# mistygro_easyeda_2023-10-08.net
KiCad netlist of a schematic drawn in EasyEDA
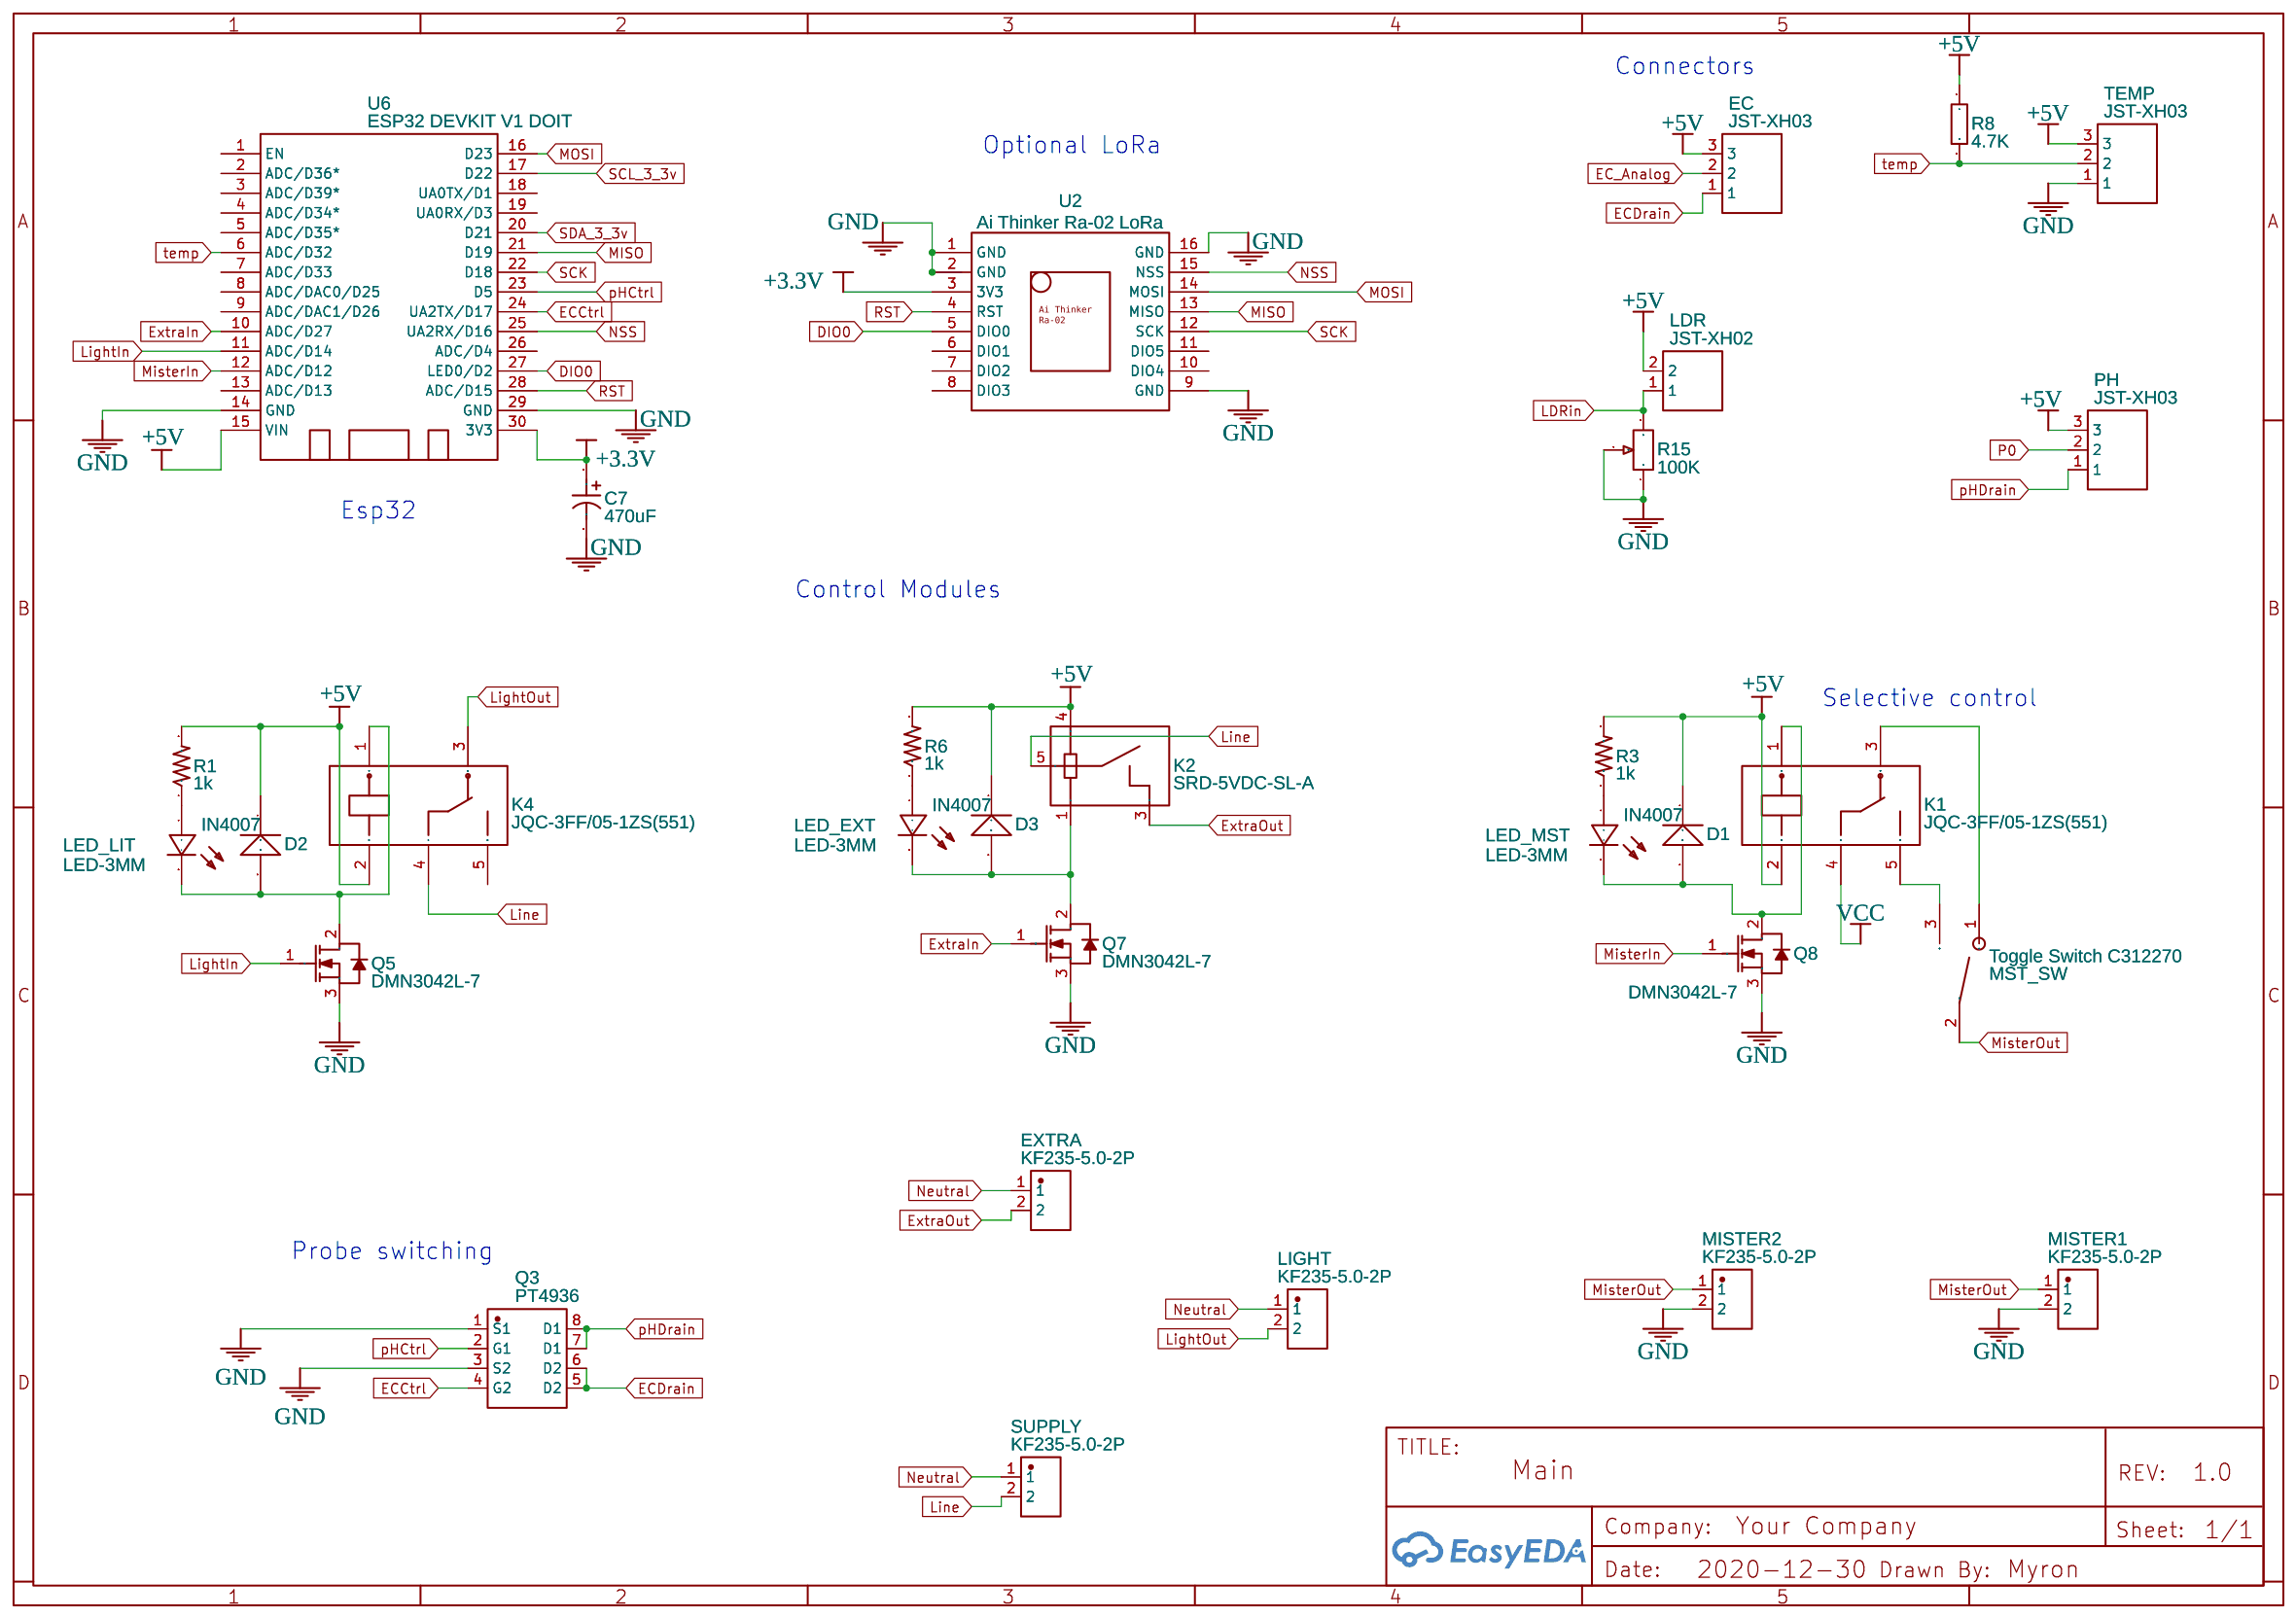
[diagram p0: Main]
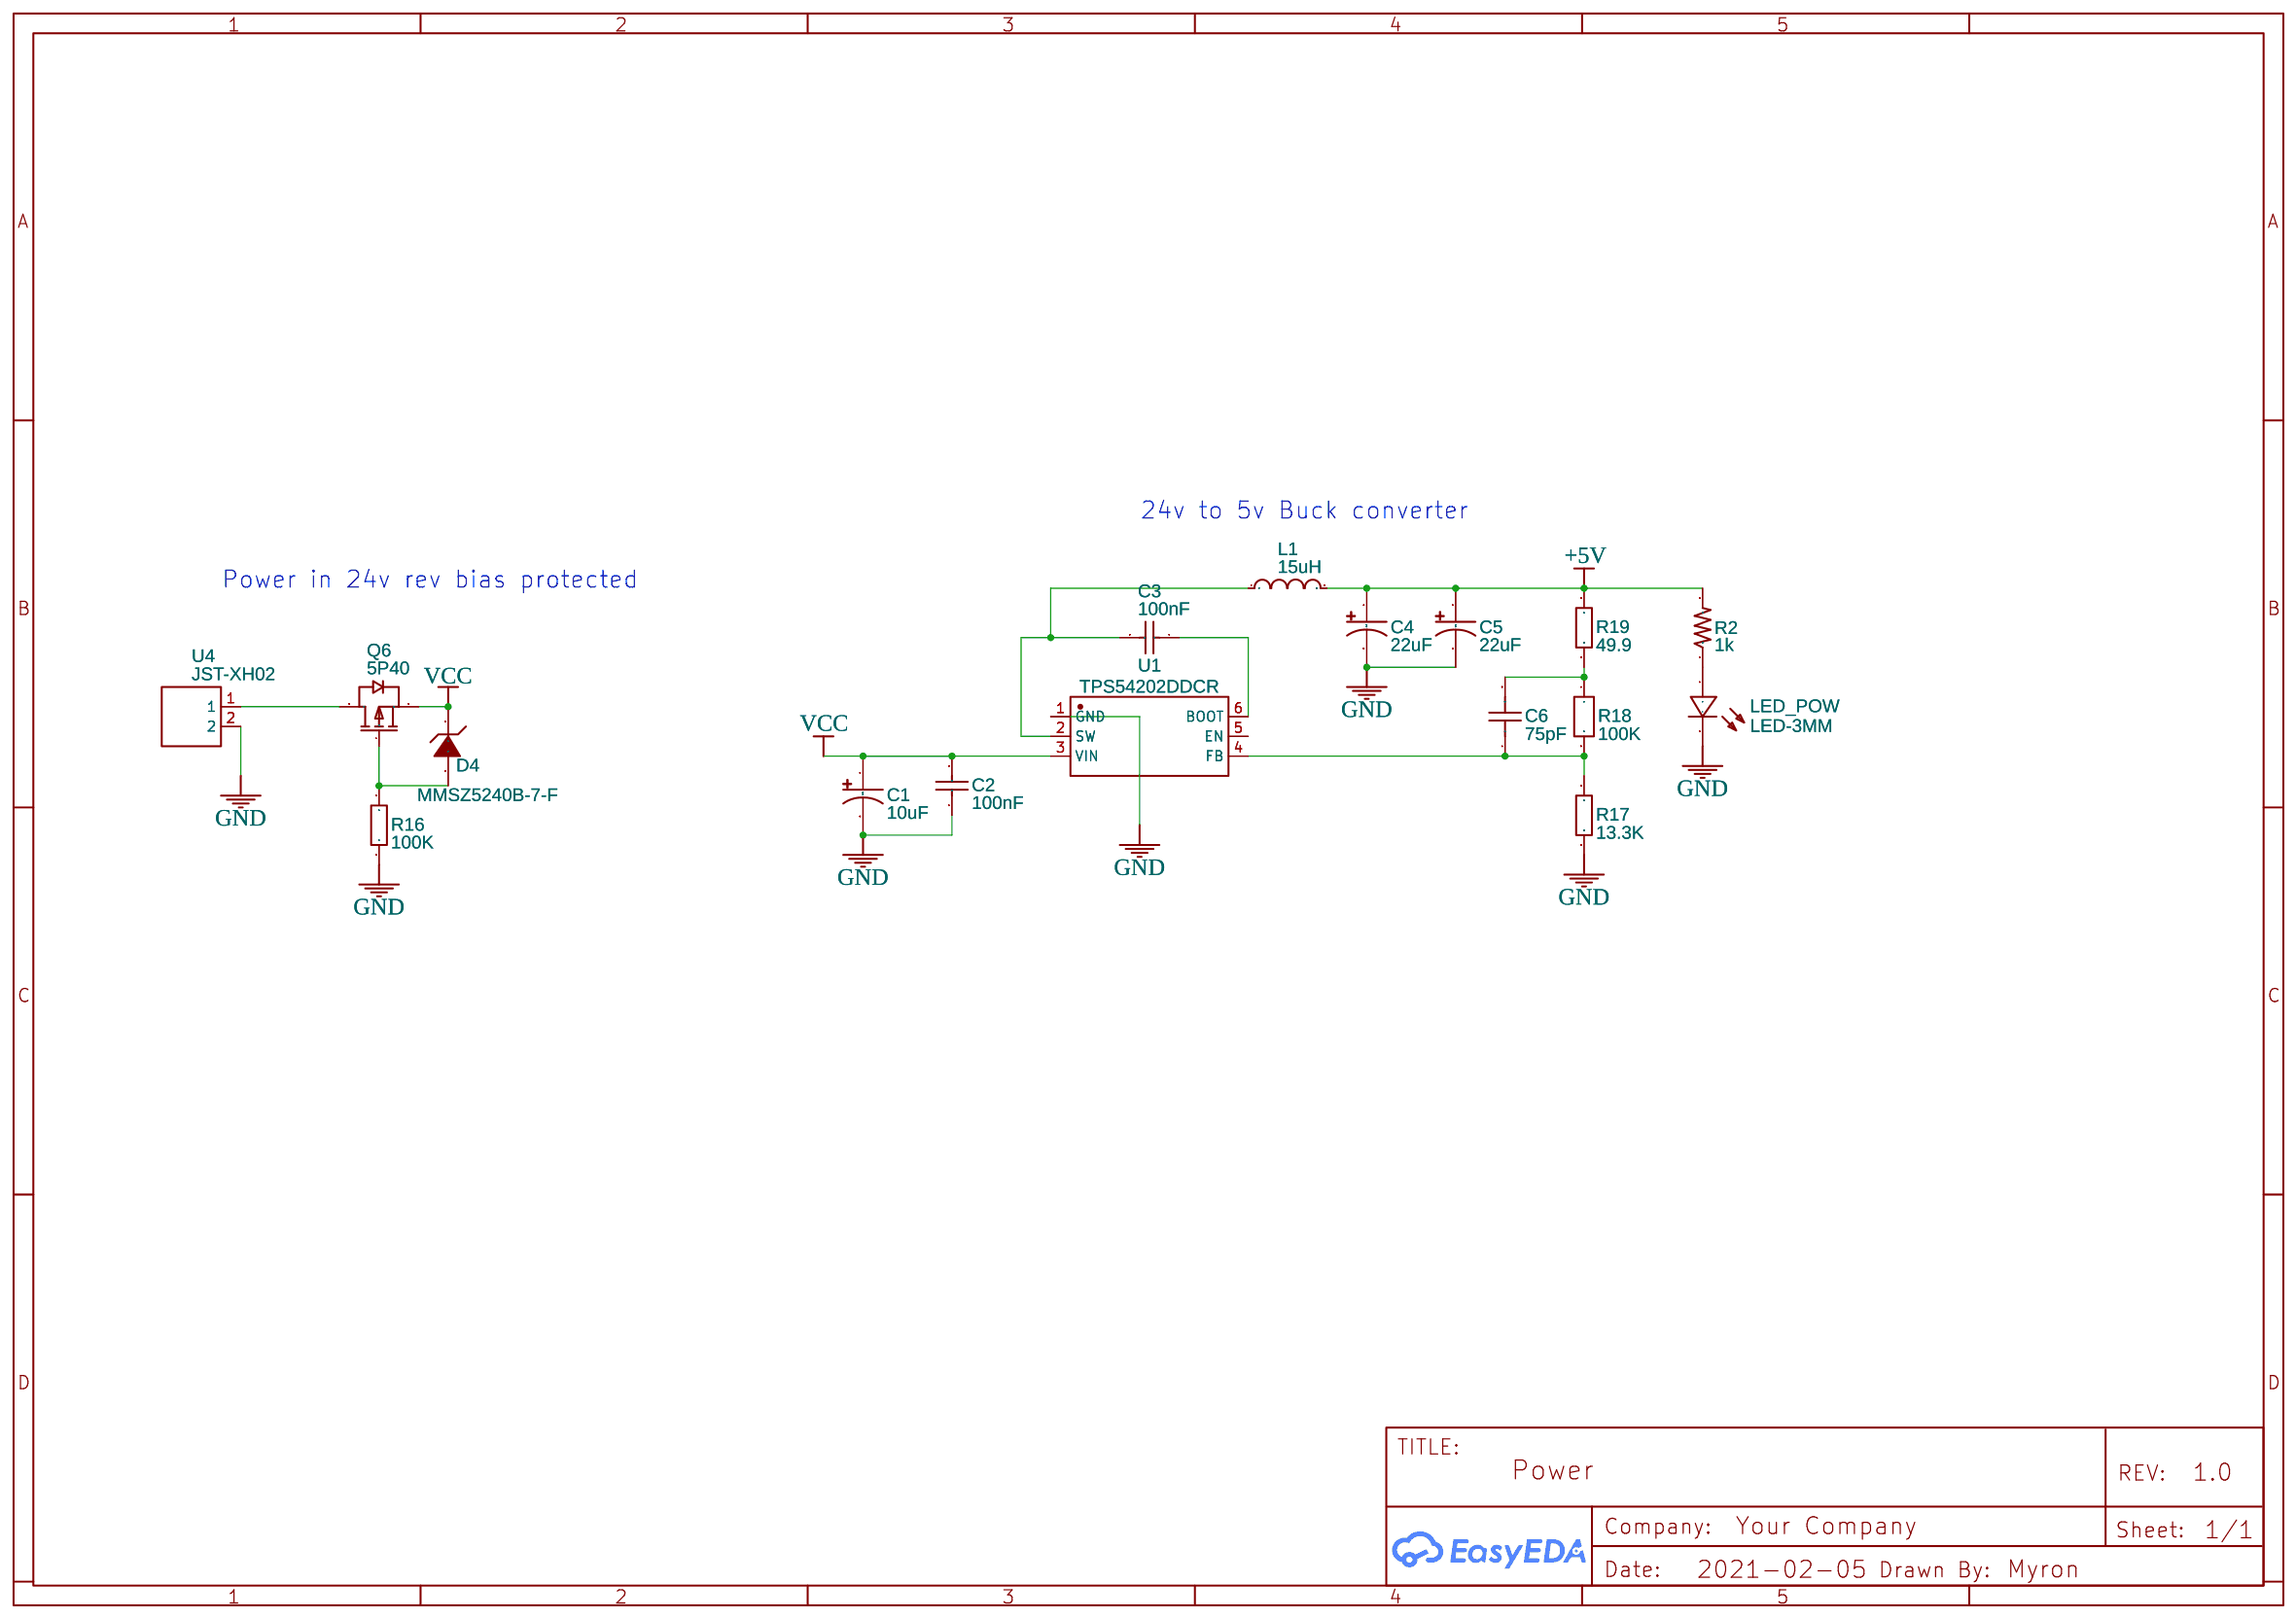
[diagram p1: Power]
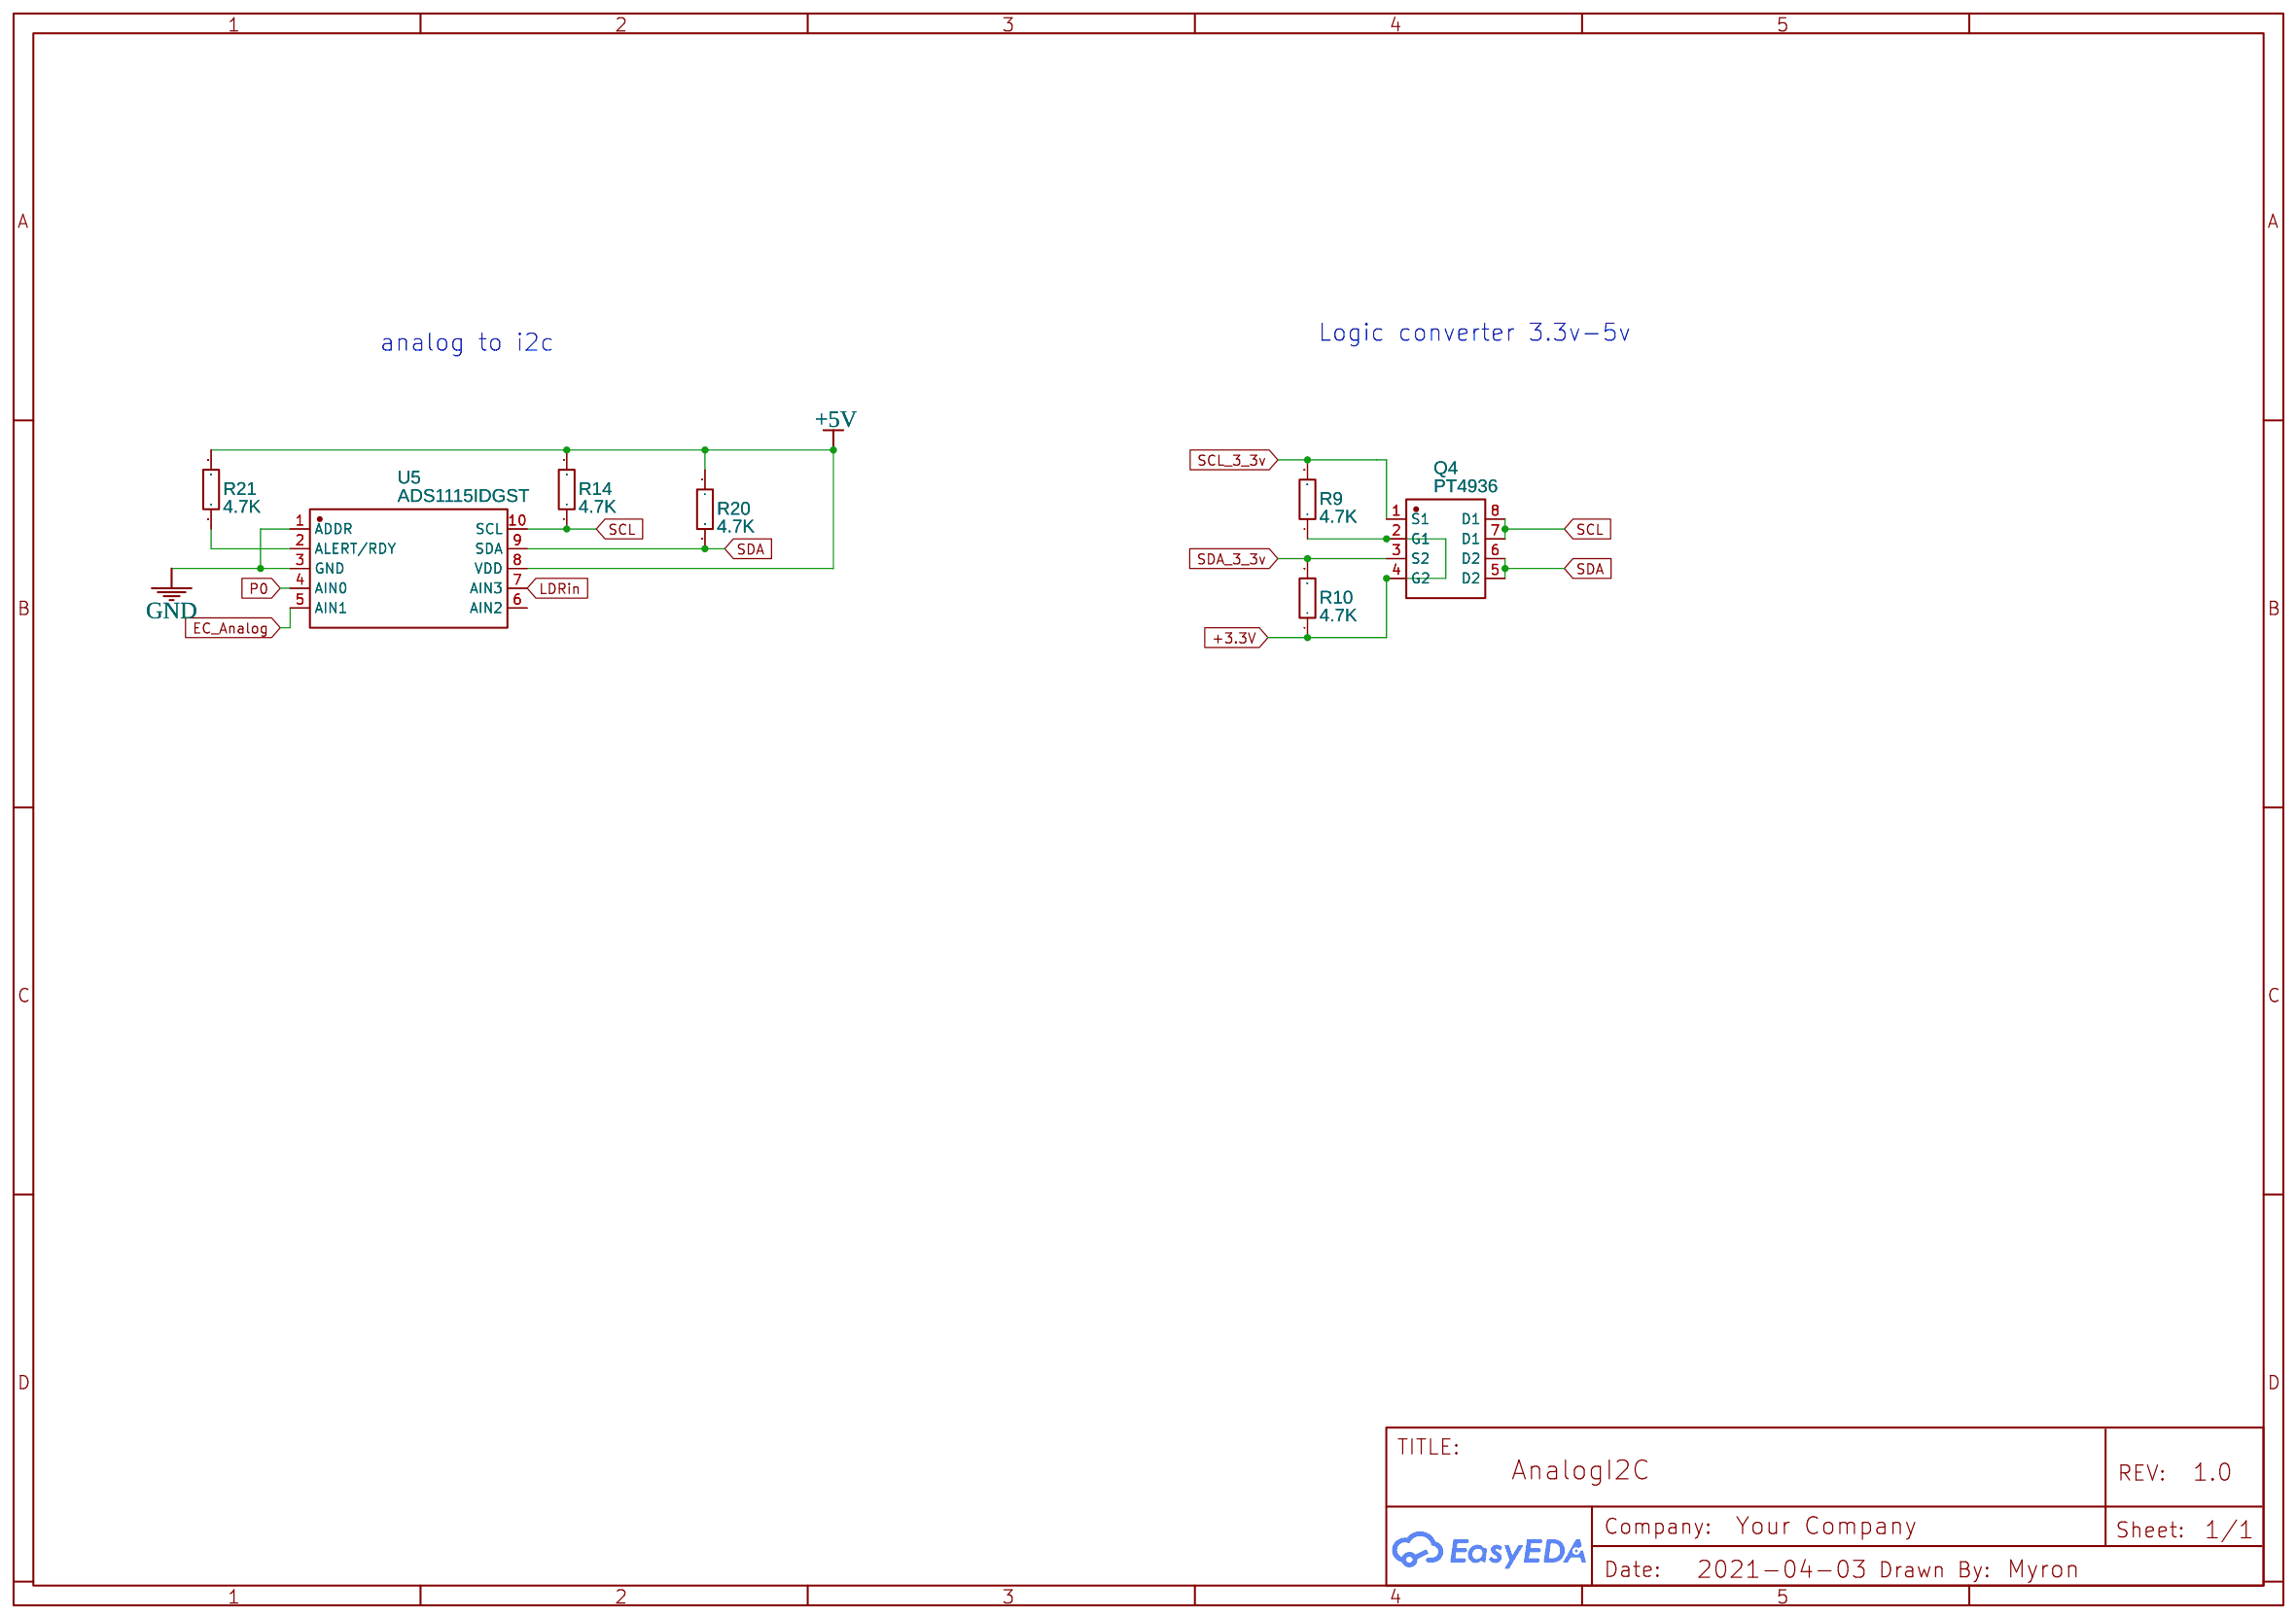
[diagram p2: AnalogI2C]

(export (version "E")
  (design (tool "Eeschema 10.0.6"))
  (components
    (comp (ref "C7")
      (value "470uF")
      (fields (field (name "Manufacturer Part") "RVT1C471M0607") (field (name "Manufacturer") "ROQANG(容强)"))
      (libsource (lib "") (part "RVT1C471M0607"))
    )
    (comp (ref "D1")
      (value "IN4007")
      (fields (field (name "Manufacturer Part") "IRFD9120PbF"))
      (libsource (lib "") (part "Unknown_845_-395"))
    )
    (comp (ref "D2")
      (value "IN4007")
      (fields (field (name "Manufacturer Part") "IRFD9120PbF"))
      (libsource (lib "") (part "Unknown_125_-390"))
    )
    (comp (ref "D3")
      (value "IN4007")
      (fields (field (name "Manufacturer Part") "IRFD9120PbF"))
      (libsource (lib "") (part "Unknown_495_-400"))
    )
    (comp (ref "EC") (value "JST-XH03") (libsource (lib "") (part "JST-XH03_1")))
    (comp (ref "EXTRA")
      (value "KF235-5.0-2P")
      (fields (field (name "Manufacturer") "Cixi Kefa Elec"))
      (libsource (lib "") (part "KF235-5.0-2P_2"))
    )
    (comp (ref "K1")
      (value "JQC-3FF/05-1ZS(551)")
      (fields
        (field (name "Manufacturer Part") "JQC-3FF/005-1ZS(551)")
        (field (name "Manufacturer") "HF(宏发)")
      )
      (libsource (lib "") (part "JQC-3FF/05-1ZS(551)"))
    )
    (comp (ref "K2")
      (value "SRD-5VDC-SL-A")
      (fields (field (name "Manufacturer") "Ningbo Songle Relay"))
      (libsource (lib "") (part "Unknown_545_-425"))
    )
    (comp (ref "K4")
      (value "JQC-3FF/05-1ZS(551)")
      (fields
        (field (name "Manufacturer Part") "JQC-3FF/005-1ZS(551)")
        (field (name "Manufacturer") "HF(宏发)")
      )
      (libsource (lib "") (part "JQC-3FF/05-1ZS(551)"))
    )
    (comp (ref "LDR") (value "JST-XH02") (libsource (lib "") (part "JST-XH02")))
    (comp (ref "LED_EXT")
      (value "LED-3MM")
      (fields
        (field (name "Manufacturer Part") "204-10SURD/S530-A3")
        (field (name "Manufacturer") "EVERLIGHT")
      )
      (libsource (lib "") (part "Unknown_460_-395"))
    )
    (comp (ref "LED_LIT")
      (value "LED-3MM")
      (fields
        (field (name "Manufacturer Part") "204-10SURD/S530-A3")
        (field (name "Manufacturer") "EVERLIGHT")
      )
      (libsource (lib "") (part "Unknown_90_-385"))
    )
    (comp (ref "LED_MST")
      (value "LED-3MM")
      (fields
        (field (name "Manufacturer Part") "204-10SURD/S530-A3")
        (field (name "Manufacturer") "EVERLIGHT")
      )
      (libsource (lib "") (part "Unknown_810_-390"))
    )
    (comp (ref "LIGHT")
      (value "KF235-5.0-2P")
      (fields (field (name "Manufacturer") "Cixi Kefa Elec"))
      (libsource (lib "") (part "KF235-5.0-2P_3"))
    )
    (comp (ref "MISTER1")
      (value "KF235-5.0-2P")
      (fields (field (name "Manufacturer") "Cixi Kefa Elec"))
      (libsource (lib "") (part "KF235-5.0-2P"))
    )
    (comp (ref "MISTER2")
      (value "KF235-5.0-2P")
      (fields (field (name "Manufacturer") "Cixi Kefa Elec"))
      (libsource (lib "") (part "KF235-5.0-2P"))
    )
    (comp (ref "MST_SW")
      (value "Toggle Switch C312270")
      (fields
        (field (name "Manufacturer Part") "ST-1-102-A01-T000-RS")
        (field (name "Manufacturer") "YUEN FUNG")
      )
      (libsource (lib "") (part "Toggle Switch C312270"))
    )
    (comp (ref "PH") (value "JST-XH03") (libsource (lib "") (part "JST-XH03")))
    (comp (ref "Q3")
      (value "PT4936")
      (fields (field (name "Manufacturer") "PUOLOP"))
      (libsource (lib "") (part "PT4936"))
    )
    (comp (ref "Q5")
      (value "DMN3042L-7")
      (fields (field (name "Manufacturer") "Diodes Incorporated"))
      (libsource (lib "") (part "DMN3042L-7"))
    )
    (comp (ref "Q7")
      (value "DMN3042L-7")
      (fields (field (name "Manufacturer") "Diodes Incorporated"))
      (libsource (lib "") (part "DMN3042L-7"))
    )
    (comp (ref "Q8")
      (value "DMN3042L-7")
      (fields (field (name "Manufacturer") "Diodes Incorporated"))
      (libsource (lib "") (part "DMN3042L-7"))
    )
    (comp (ref "R1")
      (value "1k")
      (fields (field (name "Manufacturer Part") "?"))
      (libsource (lib "") (part "Unknown_85_-425"))
    )
    (comp (ref "R3")
      (value "1k")
      (fields (field (name "Manufacturer Part") "?"))
      (libsource (lib "") (part "Unknown_805_-430"))
    )
    (comp (ref "R6")
      (value "1k")
      (fields (field (name "Manufacturer Part") "?"))
      (libsource (lib "") (part "Unknown_455_-435"))
    )
    (comp (ref "R8")
      (value "4.7K")
      (fields
        (field (name "Manufacturer Part") "CRCW12064K70FKEA")
        (field (name "Manufacturer") "Vishay Intertech")
      )
      (libsource (lib "") (part "CRCW12064K70FKEA"))
    )
    (comp (ref "R15")
      (value "100K")
      (fields
        (field (name "Manufacturer Part") "3296W-1-104")
        (field (name "Manufacturer") "Chengdu Guosheng Tech")
      )
      (libsource (lib "") (part "3296W-1-104"))
    )
    (comp (ref "SUPPLY")
      (value "KF235-5.0-2P")
      (fields (field (name "Manufacturer") "Cixi Kefa Elec"))
      (libsource (lib "") (part "KF235-5.0-2P_1"))
    )
    (comp (ref "TEMP") (value "JST-XH03") (libsource (lib "") (part "JST-XH03_2")))
    (comp (ref "U2") (value "Ai Thinker Ra-02 LoRa") (libsource (lib "") (part "Ai Thinker Ra-02 LoRa")))
    (comp (ref "U6") (value "ESP32 DEVKIT V1 DOIT") (libsource (lib "") (part "ESP32 DEVKIT V1 DOIT")))
    (comp (ref "C1")
      (value "10uF")
      (fields (field (name "Manufacturer Part") "EEEHB1V100AR") (field (name "Manufacturer") "PANASONIC"))
      (libsource (lib "") (part "EEEHB1V100AR"))
    )
    (comp (ref "C2")
      (value "100nF")
      (fields (field (name "Manufacturer Part") "CL31B104KBCNNNC") (field (name "Manufacturer") "SAMSUNG"))
      (libsource (lib "") (part "CL31B104KBCNNNC"))
    )
    (comp (ref "C3")
      (value "100nF")
      (fields (field (name "Manufacturer Part") "CL31B104KBCNNNC") (field (name "Manufacturer") "SAMSUNG"))
      (libsource (lib "") (part "CL31B104KBCNNNC_1"))
    )
    (comp (ref "C4")
      (value "22uF")
      (fields (field (name "Manufacturer Part") "CK1V220M-CRE54") (field (name "Manufacturer") "Semtech"))
      (libsource (lib "") (part "CK1V220M-CRE54"))
    )
    (comp (ref "C5")
      (value "22uF")
      (fields (field (name "Manufacturer Part") "CK1V220M-CRE54") (field (name "Manufacturer") "Semtech"))
      (libsource (lib "") (part "CK1V220M-CRE54"))
    )
    (comp (ref "C6")
      (value "75pF")
      (fields (field (name "Manufacturer Part") "CC0805JRNPO9BN750") (field (name "Manufacturer") "YAGEO"))
      (libsource (lib "") (part "CC0805JRNPO9BN750"))
    )
    (comp (ref "D4")
      (value "MMSZ5240B-7-F")
      (fields (field (name "Manufacturer") "DIODES"))
      (libsource (lib "") (part "MMSZ5240B-7-F"))
    )
    (comp (ref "L1")
      (value "15uH")
      (fields (field (name "Manufacturer Part") "CR5040-150M") (field (name "Manufacturer") "Ceaiya"))
      (libsource (lib "") (part "CR5040-150M"))
    )
    (comp (ref "LED_POW")
      (value "LED-3MM")
      (fields
        (field (name "Manufacturer Part") "204-10SURD/S530-A3")
        (field (name "Manufacturer") "EVERLIGHT")
      )
      (libsource (lib "") (part "Unknown_860_-455"))
    )
    (comp (ref "Q6")
      (value "5P40")
      (fields (field (name "Manufacturer") "GOFORD"))
      (libsource (lib "") (part "5P40"))
    )
    (comp (ref "R2")
      (value "1k")
      (fields (field (name "Manufacturer Part") "?"))
      (libsource (lib "") (part "Unknown_855_-495"))
    )
    (comp (ref "R16")
      (value "100K")
      (fields (field (name "Manufacturer Part") "AR06FTCV1003") (field (name "Manufacturer") "Viking Tech"))
      (libsource (lib "") (part "AR06FTCV1003"))
    )
    (comp (ref "R17")
      (value "13.3K")
      (fields
        (field (name "Manufacturer Part") "TR1206B13K3P0550")
        (field (name "Manufacturer") "Ever Ohms Tech")
      )
      (libsource (lib "") (part "TR1206B13K3P0550"))
    )
    (comp (ref "R18")
      (value "100K")
      (fields
        (field (name "Manufacturer Part") "TC0650F1003T5E")
        (field (name "Manufacturer") "UNI-ROYAL(Uniroyal Elec)")
      )
      (libsource (lib "") (part "TC0650F1003T5E"))
    )
    (comp (ref "R19")
      (value "49.9")
      (fields (field (name "Manufacturer Part") "TC0525F499JT5E") (field (name "Manufacturer") "UniOhm"))
      (libsource (lib "") (part "TC0525F499JT5E"))
    )
    (comp (ref "U1")
      (value "TPS54202DDCR")
      (fields (field (name "Manufacturer") "Texas Instruments"))
      (libsource (lib "") (part "TPS54202DDCR"))
    )
    (comp (ref "U4") (value "JST-XH02") (libsource (lib "") (part "JST-XH02")))
    (comp (ref "Q4")
      (value "PT4936")
      (fields (field (name "Manufacturer") "PUOLOP"))
      (libsource (lib "") (part "PT4936"))
    )
    (comp (ref "R9")
      (value "4.7K")
      (fields
        (field (name "Manufacturer Part") "CRCW12064K70FKEA")
        (field (name "Manufacturer") "Vishay Intertech")
      )
      (libsource (lib "") (part "CRCW12064K70FKEA"))
    )
    (comp (ref "R10")
      (value "4.7K")
      (fields
        (field (name "Manufacturer Part") "CRCW12064K70FKEA")
        (field (name "Manufacturer") "Vishay Intertech")
      )
      (libsource (lib "") (part "CRCW12064K70FKEA"))
    )
    (comp (ref "R14")
      (value "4.7K")
      (fields
        (field (name "Manufacturer Part") "CRCW12064K70FKEA")
        (field (name "Manufacturer") "Vishay Intertech")
      )
      (libsource (lib "") (part "CRCW12064K70FKEA"))
    )
    (comp (ref "R20")
      (value "4.7K")
      (fields
        (field (name "Manufacturer Part") "CRCW12064K70FKEA")
        (field (name "Manufacturer") "Vishay Intertech")
      )
      (libsource (lib "") (part "CRCW12064K70FKEA_1"))
    )
    (comp (ref "R21")
      (value "4.7K")
      (fields
        (field (name "Manufacturer Part") "CRCW12064K70FKEA")
        (field (name "Manufacturer") "Vishay Intertech")
      )
      (libsource (lib "") (part "CRCW12064K70FKEA"))
    )
    (comp (ref "U5")
      (value "ADS1115IDGST")
      (fields (field (name "Manufacturer") "Texas Instruments"))
      (libsource (lib "") (part "ADS1115IDGST"))
    )
  )
  (nets
    (net (code "1") (name "+3.3V") (class "Default")
      (node (ref "C7") (pin "1") (pinfunction "1_1") (pintype "input"))
      (node (ref "Q4") (pin "2") (pinfunction "G1_2") (pintype "unspecified"))
      (node (ref "Q4") (pin "4") (pinfunction "G2_4") (pintype "unspecified"))
      (node (ref "R10") (pin "1") (pinfunction "1_1") (pintype "unspecified"))
      (node (ref "R9") (pin "1") (pinfunction "1_1") (pintype "unspecified"))
      (node (ref "U2") (pin "3") (pinfunction "3V3_3") (pintype "unspecified"))
      (node (ref "U6") (pin "30") (pinfunction "3V3_30") (pintype "bidirectional"))
    )
    (net (code "2") (name "+5V") (class "Default")
      (node (ref "C4") (pin "1") (pinfunction "1_1") (pintype "unspecified"))
      (node (ref "C5") (pin "1") (pinfunction "1_1") (pintype "unspecified"))
      (node (ref "D1") (pin "1") (pinfunction "1_1") (pintype "unspecified"))
      (node (ref "D2") (pin "1") (pinfunction "1_1") (pintype "unspecified"))
      (node (ref "D3") (pin "1") (pinfunction "1_1") (pintype "unspecified"))
      (node (ref "EC") (pin "3") (pinfunction "3_3") (pintype "unspecified"))
      (node (ref "K1") (pin "2") (pinfunction "2_2") (pintype "input"))
      (node (ref "K2") (pin "4") (pinfunction "4_4") (pintype "unspecified"))
      (node (ref "K4") (pin "2") (pinfunction "2_2") (pintype "input"))
      (node (ref "L1") (pin "2") (pinfunction "2_2") (pintype "unspecified"))
      (node (ref "LDR") (pin "2") (pinfunction "2_2") (pintype "unspecified"))
      (node (ref "PH") (pin "3") (pinfunction "3_3") (pintype "unspecified"))
      (node (ref "R1") (pin "2") (pinfunction "2_2") (pintype "unspecified"))
      (node (ref "R14") (pin "2") (pinfunction "2_2") (pintype "unspecified"))
      (node (ref "R19") (pin "1") (pinfunction "1_1") (pintype "input"))
      (node (ref "R2") (pin "2") (pinfunction "2_2") (pintype "unspecified"))
      (node (ref "R20") (pin "1") (pinfunction "1_1") (pintype "unspecified"))
      (node (ref "R21") (pin "2") (pinfunction "2_2") (pintype "unspecified"))
      (node (ref "R3") (pin "2") (pinfunction "2_2") (pintype "unspecified"))
      (node (ref "R6") (pin "2") (pinfunction "2_2") (pintype "unspecified"))
      (node (ref "R8") (pin "1") (pinfunction "1_1") (pintype "unspecified"))
      (node (ref "TEMP") (pin "3") (pinfunction "3_3") (pintype "unspecified"))
      (node (ref "U5") (pin "8") (pinfunction "VDD_8") (pintype "unspecified"))
      (node (ref "U6") (pin "15") (pinfunction "VIN_15") (pintype "input"))
    )
    (net (code "3") (name "DIO0") (class "Default")
      (node (ref "U2") (pin "5") (pinfunction "DIO0_5") (pintype "unspecified"))
      (node (ref "U6") (pin "27") (pinfunction "LED0/D2_27") (pintype "bidirectional"))
    )
    (net (code "4") (name "ECCtrl") (class "Default")
      (node (ref "Q3") (pin "4") (pinfunction "G2_4") (pintype "unspecified"))
      (node (ref "U6") (pin "24") (pinfunction "UA2TX/D17_24") (pintype "bidirectional"))
    )
    (net (code "5") (name "ECDrain") (class "Default")
      (node (ref "EC") (pin "1") (pinfunction "1_1") (pintype "unspecified"))
      (node (ref "Q3") (pin "5") (pinfunction "D2_5") (pintype "unspecified"))
      (node (ref "Q3") (pin "6") (pinfunction "D2_6") (pintype "unspecified"))
    )
    (net (code "6") (name "EC_Analog") (class "Default")
      (node (ref "EC") (pin "2") (pinfunction "2_2") (pintype "unspecified"))
      (node (ref "U5") (pin "5") (pinfunction "AIN1_5") (pintype "unspecified"))
    )
    (net (code "7") (name "ExtraIn") (class "Default")
      (node (ref "Q7") (pin "1") (pinfunction "G_1") (pintype "unspecified"))
      (node (ref "U6") (pin "10") (pinfunction "ADC/D27_10") (pintype "bidirectional"))
    )
    (net (code "8") (name "ExtraOut") (class "Default")
      (node (ref "EXTRA") (pin "2") (pinfunction "2_2") (pintype "unspecified"))
      (node (ref "K2") (pin "3") (pinfunction "3_3") (pintype "unspecified"))
    )
    (net (code "9") (name "GND") (class "Default")
      (node (ref "C1") (pin "2") (pinfunction "2_2") (pintype "unspecified"))
      (node (ref "C2") (pin "2") (pinfunction "2_2") (pintype "input"))
      (node (ref "C4") (pin "2") (pinfunction "2_2") (pintype "unspecified"))
      (node (ref "C5") (pin "2") (pinfunction "2_2") (pintype "unspecified"))
      (node (ref "C7") (pin "2") (pinfunction "2_2") (pintype "input"))
      (node (ref "LED_POW") (pin "2") (pinfunction "-_2") (pintype "unspecified"))
      (node (ref "MISTER1") (pin "2") (pinfunction "2_2") (pintype "unspecified"))
      (node (ref "MISTER2") (pin "2") (pinfunction "2_2") (pintype "unspecified"))
      (node (ref "Q3") (pin "1") (pinfunction "S1_1") (pintype "unspecified"))
      (node (ref "Q3") (pin "3") (pinfunction "S2_3") (pintype "unspecified"))
      (node (ref "Q5") (pin "3") (pinfunction "S_3") (pintype "unspecified"))
      (node (ref "Q7") (pin "3") (pinfunction "S_3") (pintype "unspecified"))
      (node (ref "Q8") (pin "3") (pinfunction "S_3") (pintype "unspecified"))
      (node (ref "R15") (pin "1") (pinfunction "1_1") (pintype "input"))
      (node (ref "R15") (pin "2") (pinfunction "2_2") (pintype "input"))
      (node (ref "R16") (pin "1") (pinfunction "1_1") (pintype "unspecified"))
      (node (ref "R17") (pin "2") (pinfunction "2_2") (pintype "unspecified"))
      (node (ref "TEMP") (pin "1") (pinfunction "1_1") (pintype "unspecified"))
      (node (ref "U1") (pin "1") (pinfunction "GND_1") (pintype "unspecified"))
      (node (ref "U2") (pin "1") (pinfunction "GND_1") (pintype "unspecified"))
      (node (ref "U2") (pin "16") (pinfunction "GND_16") (pintype "unspecified"))
      (node (ref "U2") (pin "2") (pinfunction "GND_2") (pintype "unspecified"))
      (node (ref "U2") (pin "9") (pinfunction "GND_9") (pintype "unspecified"))
      (node (ref "U4") (pin "2") (pinfunction "2_2") (pintype "unspecified"))
      (node (ref "U5") (pin "1") (pinfunction "ADDR_1") (pintype "unspecified"))
      (node (ref "U5") (pin "3") (pinfunction "GND_3") (pintype "unspecified"))
      (node (ref "U6") (pin "14") (pinfunction "GND_14") (pintype "bidirectional"))
      (node (ref "U6") (pin "29") (pinfunction "GND_29") (pintype "bidirectional"))
    )
    (net (code "10") (name "LDRin") (class "Default")
      (node (ref "LDR") (pin "1") (pinfunction "1_1") (pintype "unspecified"))
      (node (ref "R15") (pin "3") (pinfunction "3_3") (pintype "input"))
      (node (ref "U5") (pin "7") (pinfunction "AIN3_7") (pintype "unspecified"))
    )
    (net (code "11") (name "LightIn") (class "Default")
      (node (ref "Q5") (pin "1") (pinfunction "G_1") (pintype "unspecified"))
      (node (ref "U6") (pin "11") (pinfunction "ADC/D14_11") (pintype "bidirectional"))
    )
    (net (code "12") (name "LightOut") (class "Default")
      (node (ref "K4") (pin "3") (pinfunction "3_3") (pintype "input"))
      (node (ref "LIGHT") (pin "2") (pinfunction "2_2") (pintype "unspecified"))
    )
    (net (code "13") (name "Line") (class "Default")
      (node (ref "K2") (pin "5") (pinfunction "5_5") (pintype "unspecified"))
      (node (ref "K4") (pin "4") (pinfunction "4_4") (pintype "input"))
      (node (ref "SUPPLY") (pin "2") (pinfunction "2_2") (pintype "unspecified"))
    )
    (net (code "14") (name "MISO") (class "Default")
      (node (ref "U2") (pin "13") (pinfunction "MISO_13") (pintype "unspecified"))
      (node (ref "U6") (pin "21") (pinfunction "D19_21") (pintype "bidirectional"))
    )
    (net (code "15") (name "MOSI") (class "Default")
      (node (ref "U2") (pin "14") (pinfunction "MOSI_14") (pintype "unspecified"))
      (node (ref "U6") (pin "16") (pinfunction "D23_16") (pintype "bidirectional"))
    )
    (net (code "16") (name "MisterIn") (class "Default")
      (node (ref "Q8") (pin "1") (pinfunction "G_1") (pintype "unspecified"))
      (node (ref "U6") (pin "12") (pinfunction "ADC/D12_12") (pintype "bidirectional"))
    )
    (net (code "17") (name "MisterOut") (class "Default")
      (node (ref "MISTER1") (pin "1") (pinfunction "1_1") (pintype "unspecified"))
      (node (ref "MISTER2") (pin "1") (pinfunction "1_1") (pintype "unspecified"))
      (node (ref "MST_SW") (pin "2") (pinfunction "2_2") (pintype "input"))
    )
    (net (code "18") (name "NSS") (class "Default")
      (node (ref "U2") (pin "15") (pinfunction "NSS_15") (pintype "unspecified"))
      (node (ref "U6") (pin "25") (pinfunction "UA2RX/D16_25") (pintype "bidirectional"))
    )
    (net (code "19") (name "Net-(C6-Pad2)") (class "Default")
      (node (ref "C6") (pin "2") (pinfunction "2_2") (pintype "unspecified"))
      (node (ref "R18") (pin "1") (pinfunction "1_1") (pintype "unspecified"))
      (node (ref "R19") (pin "2") (pinfunction "2_2") (pintype "input"))
    )
    (net (code "20") (name "Net-(D4-A)") (class "Default")
      (node (ref "D4") (pin "2") (pinfunction "A_2") (pintype "unspecified"))
      (node (ref "Q6") (pin "1") (pinfunction "G_1") (pintype "unspecified"))
      (node (ref "R16") (pin "2") (pinfunction "2_2") (pintype "unspecified"))
    )
    (net (code "21") (name "Net-(K1-Pad3)") (class "Default")
      (node (ref "K1") (pin "3") (pinfunction "3_3") (pintype "input"))
      (node (ref "MST_SW") (pin "1") (pinfunction "1_1") (pintype "input"))
    )
    (net (code "22") (name "Net-(K1-Pad5)") (class "Default")
      (node (ref "K1") (pin "5") (pinfunction "5_5") (pintype "input"))
      (node (ref "MST_SW") (pin "3") (pinfunction "3_3") (pintype "input"))
    )
    (net (code "23") (name "Net-(LED_EXT-+)") (class "Default")
      (node (ref "LED_EXT") (pin "1") (pinfunction "+_1") (pintype "unspecified"))
      (node (ref "R6") (pin "1") (pinfunction "1_1") (pintype "unspecified"))
    )
    (net (code "24") (name "Net-(LED_EXT--)") (class "Default")
      (node (ref "D3") (pin "2") (pinfunction "2_2") (pintype "unspecified"))
      (node (ref "K2") (pin "1") (pinfunction "1_1") (pintype "unspecified"))
      (node (ref "LED_EXT") (pin "2") (pinfunction "-_2") (pintype "unspecified"))
      (node (ref "Q7") (pin "2") (pinfunction "D_2") (pintype "unspecified"))
    )
    (net (code "25") (name "Net-(LED_LIT-+)") (class "Default")
      (node (ref "LED_LIT") (pin "1") (pinfunction "+_1") (pintype "unspecified"))
      (node (ref "R1") (pin "1") (pinfunction "1_1") (pintype "unspecified"))
    )
    (net (code "26") (name "Net-(LED_LIT--)") (class "Default")
      (node (ref "D2") (pin "2") (pinfunction "2_2") (pintype "unspecified"))
      (node (ref "K4") (pin "1") (pinfunction "1_1") (pintype "input"))
      (node (ref "LED_LIT") (pin "2") (pinfunction "-_2") (pintype "unspecified"))
      (node (ref "Q5") (pin "2") (pinfunction "D_2") (pintype "unspecified"))
    )
    (net (code "27") (name "Net-(LED_MST-+)") (class "Default")
      (node (ref "LED_MST") (pin "1") (pinfunction "+_1") (pintype "unspecified"))
      (node (ref "R3") (pin "1") (pinfunction "1_1") (pintype "unspecified"))
    )
    (net (code "28") (name "Net-(LED_MST--)") (class "Default")
      (node (ref "D1") (pin "2") (pinfunction "2_2") (pintype "unspecified"))
      (node (ref "K1") (pin "1") (pinfunction "1_1") (pintype "input"))
      (node (ref "LED_MST") (pin "2") (pinfunction "-_2") (pintype "unspecified"))
      (node (ref "Q8") (pin "2") (pinfunction "D_2") (pintype "unspecified"))
    )
    (net (code "29") (name "Net-(LED_POW-+)") (class "Default")
      (node (ref "LED_POW") (pin "1") (pinfunction "+_1") (pintype "unspecified"))
      (node (ref "R2") (pin "1") (pinfunction "1_1") (pintype "unspecified"))
    )
    (net (code "30") (name "Net-(Q6-D)") (class "Default")
      (node (ref "Q6") (pin "3") (pinfunction "D_3") (pintype "unspecified"))
      (node (ref "U4") (pin "1") (pinfunction "1_1") (pintype "unspecified"))
    )
    (net (code "31") (name "Net-(U1-BOOT)") (class "Default")
      (node (ref "C3") (pin "1") (pinfunction "1_1") (pintype "input"))
      (node (ref "U1") (pin "6") (pinfunction "BOOT_6") (pintype "unspecified"))
    )
    (net (code "32") (name "Net-(U1-FB)") (class "Default")
      (node (ref "C6") (pin "1") (pinfunction "1_1") (pintype "unspecified"))
      (node (ref "R17") (pin "1") (pinfunction "1_1") (pintype "unspecified"))
      (node (ref "R18") (pin "2") (pinfunction "2_2") (pintype "unspecified"))
      (node (ref "U1") (pin "4") (pinfunction "FB_4") (pintype "unspecified"))
    )
    (net (code "33") (name "Net-(U1-SW)") (class "Default")
      (node (ref "C3") (pin "2") (pinfunction "2_2") (pintype "input"))
      (node (ref "L1") (pin "1") (pinfunction "1_1") (pintype "unspecified"))
      (node (ref "U1") (pin "2") (pinfunction "SW_2") (pintype "unspecified"))
    )
    (net (code "34") (name "Net-(U5-ALERT{slash}RDY)") (class "Default")
      (node (ref "R21") (pin "1") (pinfunction "1_1") (pintype "unspecified"))
      (node (ref "U5") (pin "2") (pinfunction "ALERT/RDY_2") (pintype "unspecified"))
    )
    (net (code "35") (name "Neutral") (class "Default")
      (node (ref "EXTRA") (pin "1") (pinfunction "1_1") (pintype "unspecified"))
      (node (ref "LIGHT") (pin "1") (pinfunction "1_1") (pintype "unspecified"))
      (node (ref "SUPPLY") (pin "1") (pinfunction "1_1") (pintype "unspecified"))
    )
    (net (code "36") (name "P0") (class "Default")
      (node (ref "PH") (pin "2") (pinfunction "2_2") (pintype "unspecified"))
      (node (ref "U5") (pin "4") (pinfunction "AIN0_4") (pintype "unspecified"))
    )
    (net (code "37") (name "RST") (class "Default")
      (node (ref "U2") (pin "4") (pinfunction "RST_4") (pintype "unspecified"))
      (node (ref "U6") (pin "28") (pinfunction "ADC/D15_28") (pintype "bidirectional"))
    )
    (net (code "38") (name "SCK") (class "Default")
      (node (ref "U2") (pin "12") (pinfunction "SCK_12") (pintype "unspecified"))
      (node (ref "U6") (pin "22") (pinfunction "D18_22") (pintype "bidirectional"))
    )
    (net (code "39") (name "SCL") (class "Default")
      (node (ref "Q4") (pin "7") (pinfunction "D1_7") (pintype "unspecified"))
      (node (ref "Q4") (pin "8") (pinfunction "D1_8") (pintype "unspecified"))
      (node (ref "R14") (pin "1") (pinfunction "1_1") (pintype "unspecified"))
      (node (ref "U5") (pin "10") (pinfunction "SCL_10") (pintype "unspecified"))
    )
    (net (code "40") (name "SCL_3_3v") (class "Default")
      (node (ref "Q4") (pin "1") (pinfunction "S1_1") (pintype "unspecified"))
      (node (ref "R9") (pin "2") (pinfunction "2_2") (pintype "unspecified"))
      (node (ref "U6") (pin "17") (pinfunction "D22_17") (pintype "bidirectional"))
    )
    (net (code "41") (name "SDA") (class "Default")
      (node (ref "Q4") (pin "5") (pinfunction "D2_5") (pintype "unspecified"))
      (node (ref "Q4") (pin "6") (pinfunction "D2_6") (pintype "unspecified"))
      (node (ref "R20") (pin "2") (pinfunction "2_2") (pintype "unspecified"))
      (node (ref "U5") (pin "9") (pinfunction "SDA_9") (pintype "unspecified"))
    )
    (net (code "42") (name "SDA_3_3v") (class "Default")
      (node (ref "Q4") (pin "3") (pinfunction "S2_3") (pintype "unspecified"))
      (node (ref "R10") (pin "2") (pinfunction "2_2") (pintype "unspecified"))
      (node (ref "U6") (pin "20") (pinfunction "D21_20") (pintype "bidirectional"))
    )
    (net (code "43") (name "VCC") (class "Default")
      (node (ref "C1") (pin "1") (pinfunction "1_1") (pintype "unspecified"))
      (node (ref "C2") (pin "1") (pinfunction "1_1") (pintype "input"))
      (node (ref "D4") (pin "1") (pinfunction "K_1") (pintype "unspecified"))
      (node (ref "K1") (pin "4") (pinfunction "4_4") (pintype "input"))
      (node (ref "Q6") (pin "2") (pinfunction "S_2") (pintype "unspecified"))
      (node (ref "U1") (pin "3") (pinfunction "VIN_3") (pintype "unspecified"))
    )
    (net (code "44") (name "pHCtrl") (class "Default")
      (node (ref "Q3") (pin "2") (pinfunction "G1_2") (pintype "unspecified"))
      (node (ref "U6") (pin "23") (pinfunction "D5_23") (pintype "bidirectional"))
    )
    (net (code "45") (name "pHDrain") (class "Default")
      (node (ref "PH") (pin "1") (pinfunction "1_1") (pintype "unspecified"))
      (node (ref "Q3") (pin "7") (pinfunction "D1_7") (pintype "unspecified"))
      (node (ref "Q3") (pin "8") (pinfunction "D1_8") (pintype "unspecified"))
    )
    (net (code "46") (name "temp") (class "Default")
      (node (ref "R8") (pin "2") (pinfunction "2_2") (pintype "unspecified"))
      (node (ref "TEMP") (pin "2") (pinfunction "2_2") (pintype "unspecified"))
      (node (ref "U6") (pin "6") (pinfunction "ADC/D32_6") (pintype "bidirectional"))
    )
    (net (code "47") (name "unconnected-(K4-Pad5)") (class "Default")
      (node (ref "K4") (pin "5") (pinfunction "5_5") (pintype "input"))
    )
    (net (code "48") (name "unconnected-(U1-EN-Pad5)") (class "Default")
      (node (ref "U1") (pin "5") (pinfunction "EN_5") (pintype "unspecified"))
    )
    (net (code "49") (name "unconnected-(U2-DIO1-Pad6)") (class "Default")
      (node (ref "U2") (pin "6") (pinfunction "DIO1_6") (pintype "unspecified"))
    )
    (net (code "50") (name "unconnected-(U2-DIO2-Pad7)") (class "Default")
      (node (ref "U2") (pin "7") (pinfunction "DIO2_7") (pintype "unspecified"))
    )
    (net (code "51") (name "unconnected-(U2-DIO3-Pad8)") (class "Default")
      (node (ref "U2") (pin "8") (pinfunction "DIO3_8") (pintype "unspecified"))
    )
    (net (code "52") (name "unconnected-(U2-DIO4-Pad10)") (class "Default")
      (node (ref "U2") (pin "10") (pinfunction "DIO4_10") (pintype "unspecified"))
    )
    (net (code "53") (name "unconnected-(U2-DIO5-Pad11)") (class "Default")
      (node (ref "U2") (pin "11") (pinfunction "DIO5_11") (pintype "unspecified"))
    )
    (net (code "54") (name "unconnected-(U5-AIN2-Pad6)") (class "Default")
      (node (ref "U5") (pin "6") (pinfunction "AIN2_6") (pintype "unspecified"))
    )
    (net (code "55") (name "unconnected-(U6-ADC{slash}D4-Pad26)") (class "Default")
      (node (ref "U6") (pin "26") (pinfunction "ADC/D4_26") (pintype "bidirectional"))
    )
    (net (code "56") (name "unconnected-(U6-ADC{slash}D13-Pad13)") (class "Default")
      (node (ref "U6") (pin "13") (pinfunction "ADC/D13_13") (pintype "bidirectional"))
    )
    (net (code "57") (name "unconnected-(U6-ADC{slash}D33-Pad7)") (class "Default")
      (node (ref "U6") (pin "7") (pinfunction "ADC/D33_7") (pintype "bidirectional"))
    )
    (net (code "58") (name "unconnected-(U6-ADC{slash}D34*-Pad4)") (class "Default")
      (node (ref "U6") (pin "4") (pinfunction "ADC/D34*_4") (pintype "input"))
    )
    (net (code "59") (name "unconnected-(U6-ADC{slash}D35*-Pad5)") (class "Default")
      (node (ref "U6") (pin "5") (pinfunction "ADC/D35*_5") (pintype "input"))
    )
    (net (code "60") (name "unconnected-(U6-ADC{slash}D36*-Pad2)") (class "Default")
      (node (ref "U6") (pin "2") (pinfunction "ADC/D36*_2") (pintype "input"))
    )
    (net (code "61") (name "unconnected-(U6-ADC{slash}D39*-Pad3)") (class "Default")
      (node (ref "U6") (pin "3") (pinfunction "ADC/D39*_3") (pintype "input"))
    )
    (net (code "62") (name "unconnected-(U6-ADC{slash}DAC0{slash}D25-Pad8)") (class "Default")
      (node (ref "U6") (pin "8") (pinfunction "ADC/DAC0/D25_8") (pintype "bidirectional"))
    )
    (net (code "63") (name "unconnected-(U6-ADC{slash}DAC1{slash}D26-Pad9)") (class "Default")
      (node (ref "U6") (pin "9") (pinfunction "ADC/DAC1/D26_9") (pintype "bidirectional"))
    )
    (net (code "64") (name "unconnected-(U6-EN-Pad1)") (class "Default")
      (node (ref "U6") (pin "1") (pinfunction "EN_1") (pintype "bidirectional"))
    )
    (net (code "65") (name "unconnected-(U6-UA0RX{slash}D3-Pad19)") (class "Default")
      (node (ref "U6") (pin "19") (pinfunction "UA0RX/D3_19") (pintype "bidirectional"))
    )
    (net (code "66") (name "unconnected-(U6-UA0TX{slash}D1-Pad18)") (class "Default")
      (node (ref "U6") (pin "18") (pinfunction "UA0TX/D1_18") (pintype "bidirectional"))
    )
  )
)
